# Connectors.net
KiCad netlist of a schematic drawn in Altium Designer
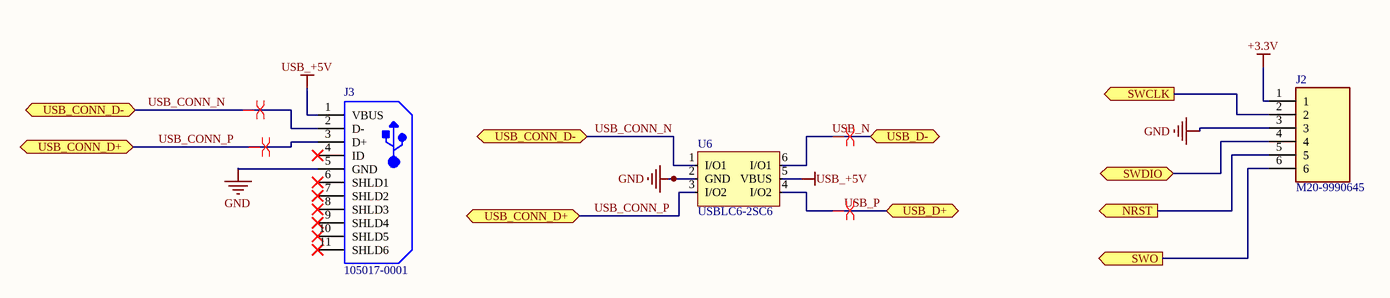
[diagram p0: Connectors.SchDoc]

(export (version "E")
  (design (tool "Eeschema 10.0.6"))
  (components
    (comp (ref "J2")
      (value "M20-9990645")
      (footprint "M20-9990645-Footprint-1")
      (libsource (lib "tutorial_PCB") (part "M20-9990645-Symbol-1"))
    )
    (comp (ref "J3")
      (value "105017-0001")
      (footprint "USB-MICRO-B_V")
      (fields (field (name "MANUFACTURER") "Molex"))
      (libsource (lib "Altium Content Vault") (part "USB-5-6SHLD"))
    )
    (comp (ref "U6")
      (value "USBLC6-2SC6")
      (footprint "STM-SOT23-6L_V")
      (description "Trans Voltage Suppressor Diode, 5V V(RWM), Unidirectional, 1 Element, Silicon")
      (libsource (lib "tutorial_PCB") (part "USBLC6-2SC6-Symbol-1"))
    )
  )
  (nets
    (net (code "1") (name "+3.3V") (class "Default")
      (node (ref "J2") (pin "1") (pinfunction "1_1") (pintype "passive"))
    )
    (net (code "3") (name "/NRST") (class "Default")
      (node (ref "J2") (pin "5") (pinfunction "5_5") (pintype "passive"))
    )
    (net (code "4") (name "/SWCLK") (class "Default")
      (node (ref "J2") (pin "2") (pinfunction "2_2") (pintype "passive"))
    )
    (net (code "5") (name "/SWDIO") (class "Default")
      (node (ref "J2") (pin "4") (pinfunction "4_4") (pintype "passive"))
    )
    (net (code "6") (name "/SWO") (class "Default")
      (node (ref "J2") (pin "6") (pinfunction "6_6") (pintype "passive"))
    )
    (net (code "7") (name "/USB_CONN_N") (class "Default")
      (node (ref "J3") (pin "2") (pinfunction "D-_2") (pintype "passive"))
      (node (ref "U6") (pin "1") (pinfunction "I/O1_1") (pintype "input"))
    )
    (net (code "8") (name "/USB_CONN_P") (class "Default")
      (node (ref "J3") (pin "3") (pinfunction "D+_3") (pintype "passive"))
      (node (ref "U6") (pin "3") (pinfunction "I/O2_3") (pintype "input"))
    )
    (net (code "9") (name "/USB_N") (class "Default")
      (node (ref "U6") (pin "6") (pinfunction "I/O1_6") (pintype "input"))
    )
    (net (code "10") (name "/USB_P") (class "Default")
      (node (ref "U6") (pin "4") (pinfunction "I/O2_4") (pintype "input"))
    )
    (net (code "11") (name "GND") (class "Default")
      (node (ref "J2") (pin "3") (pinfunction "3_3") (pintype "passive"))
      (node (ref "J3") (pin "5") (pinfunction "GND_5") (pintype "passive"))
      (node (ref "U6") (pin "2") (pinfunction "GND_2") (pintype "input"))
    )
    (net (code "12") (name "USB_+5V") (class "Default")
      (node (ref "J3") (pin "1") (pinfunction "VBUS_1") (pintype "passive"))
      (node (ref "U6") (pin "5") (pinfunction "VBUS_5") (pintype "input"))
    )
    (net (code "13") (name "unconnected-(J3-ID-Pad4)") (class "Default")
      (node (ref "J3") (pin "4") (pinfunction "ID_4") (pintype "passive+no_connect"))
    )
    (net (code "14") (name "unconnected-(J3-SHLD1-Pad6)") (class "Default")
      (node (ref "J3") (pin "6") (pinfunction "SHLD1_6") (pintype "passive+no_connect"))
    )
    (net (code "15") (name "unconnected-(J3-SHLD2-Pad7)") (class "Default")
      (node (ref "J3") (pin "7") (pinfunction "SHLD2_7") (pintype "passive+no_connect"))
    )
    (net (code "16") (name "unconnected-(J3-SHLD3-Pad8)") (class "Default")
      (node (ref "J3") (pin "8") (pinfunction "SHLD3_8") (pintype "passive+no_connect"))
    )
    (net (code "17") (name "unconnected-(J3-SHLD4-Pad9)") (class "Default")
      (node (ref "J3") (pin "9") (pinfunction "SHLD4_9") (pintype "passive+no_connect"))
    )
    (net (code "18") (name "unconnected-(J3-SHLD5-Pad10)") (class "Default")
      (node (ref "J3") (pin "10") (pinfunction "SHLD5_10") (pintype "passive+no_connect"))
    )
    (net (code "19") (name "unconnected-(J3-SHLD6-Pad11)") (class "Default")
      (node (ref "J3") (pin "11") (pinfunction "SHLD6_11") (pintype "passive+no_connect"))
    )
  )
)
